# ukmarsbot-wall-sensor-basic.net
KiCad netlist of a schematic drawn in EAGLE
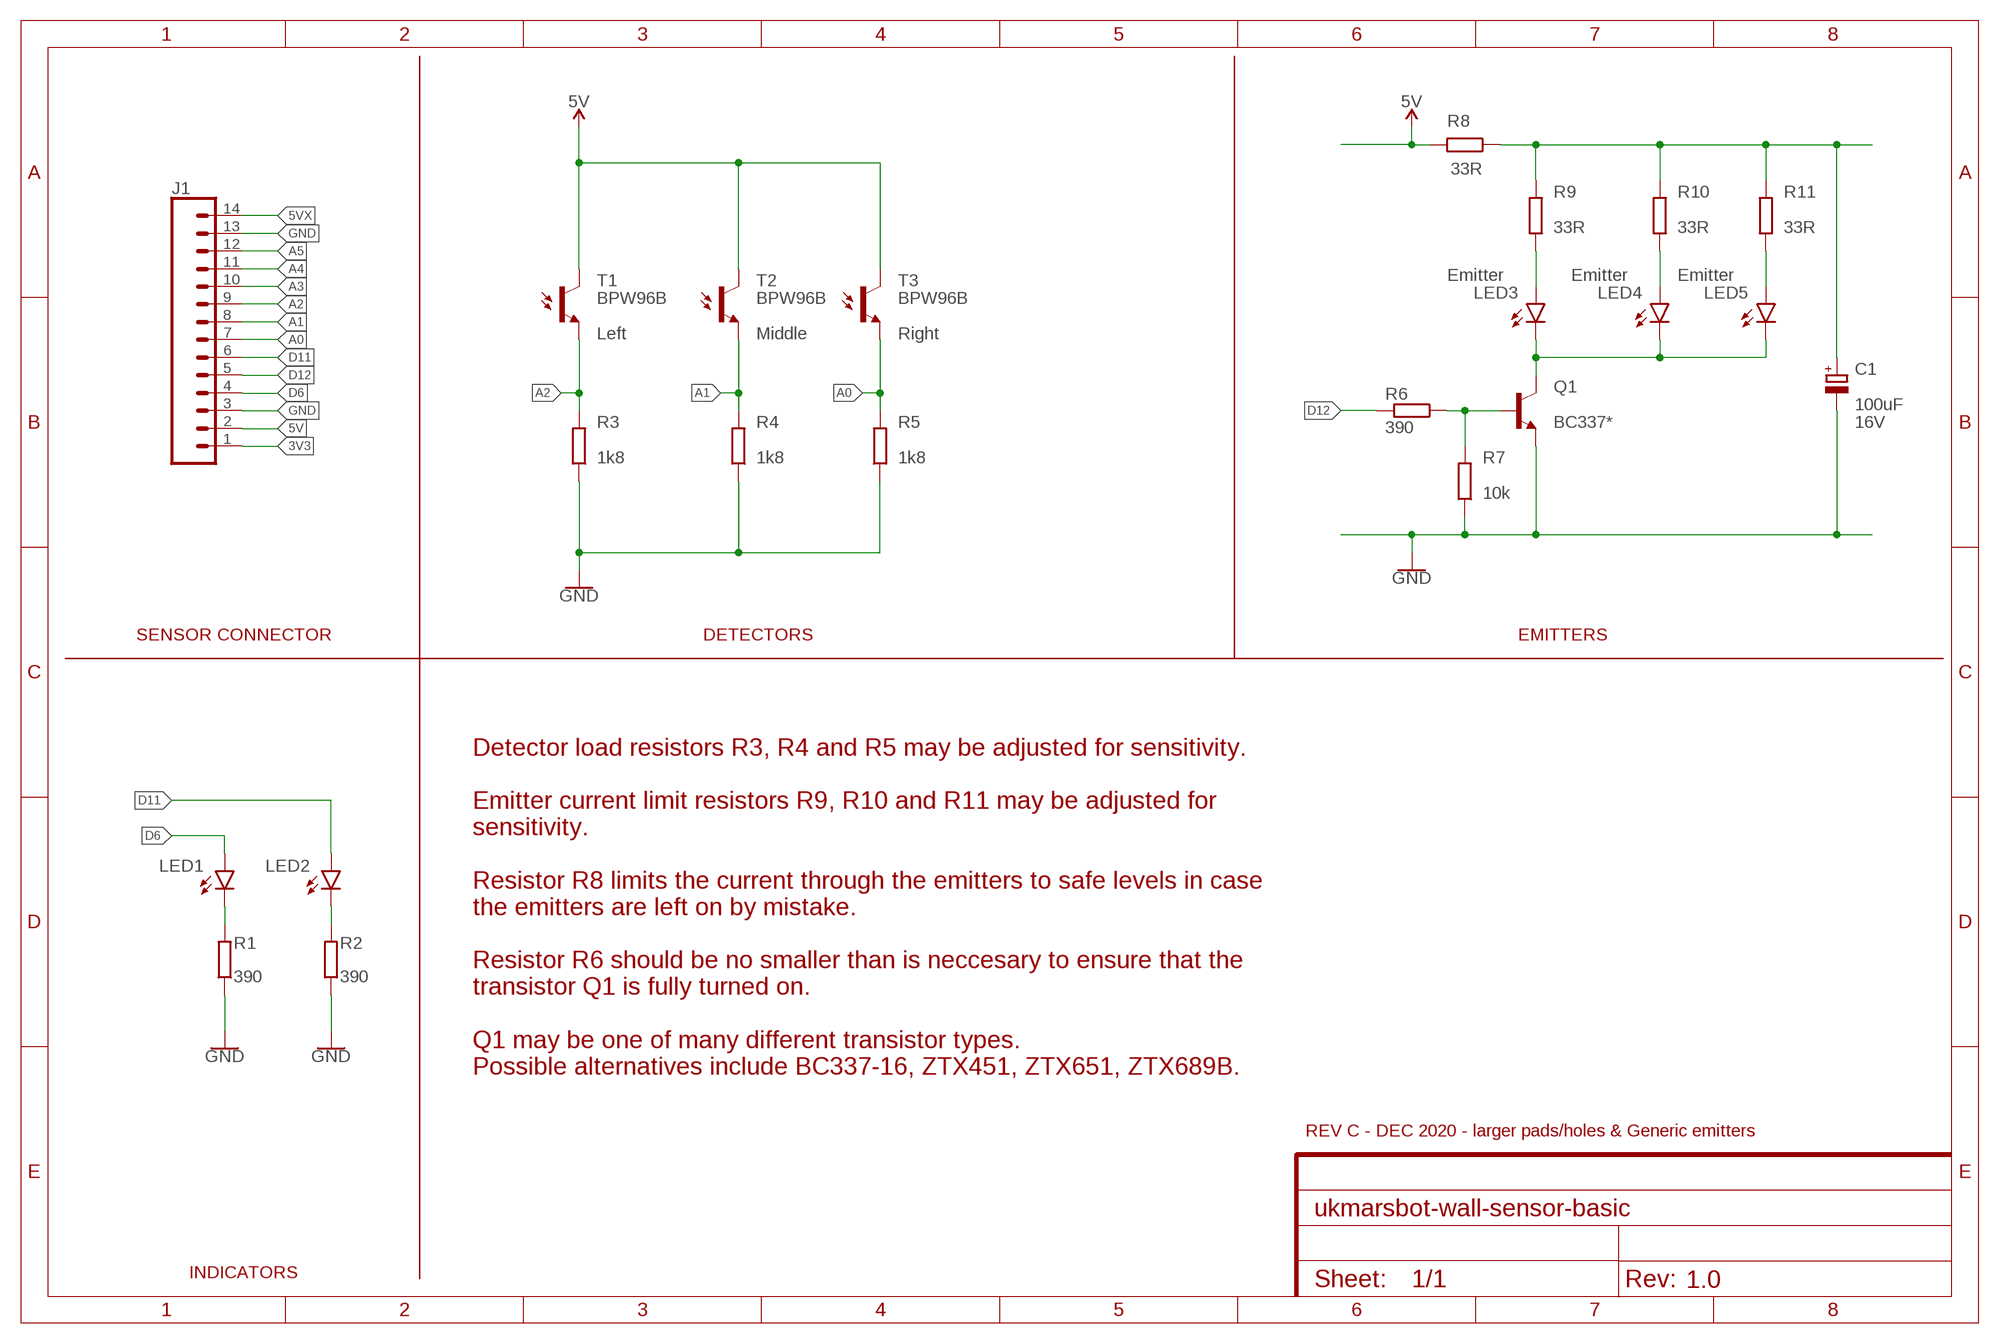
[diagram p0: schematic, sheet 1]

(export (version "E")
  (design (tool "Eeschema 10.0.6"))
  (components
    (comp (ref "C1")
      (value "100uF")
      (footprint "eagle-import:E2,5-7")
      (fields (field (name "VOLTAGE") "16V"))
      (libsource (lib "eagle-import") (part "CPOL-EUE2.5-7"))
    )
    (comp (ref "J1")
      (value "CONN_14")
      (footprint "eagle-import:1X14")
      (libsource (lib "eagle-import") (part "CONN_14"))
    )
    (comp (ref "LED1")
      (value "LED3MM")
      (footprint "eagle-import:LED_3MM")
      (libsource (lib "eagle-import") (part "LED3MM"))
    )
    (comp (ref "LED2")
      (value "LED3MM")
      (footprint "eagle-import:LED_3MM")
      (libsource (lib "eagle-import") (part "LED3MM"))
    )
    (comp (ref "LED3")
      (value "Emitter")
      (footprint "eagle-import:LED-5MM-SIDE")
      (libsource (lib "eagle-import") (part "LED-SIDE"))
    )
    (comp (ref "LED4")
      (value "Emitter")
      (footprint "eagle-import:LED-5MM-SIDE")
      (libsource (lib "eagle-import") (part "LED-SIDE"))
    )
    (comp (ref "LED5")
      (value "Emitter")
      (footprint "eagle-import:LED-5MM-SIDE")
      (libsource (lib "eagle-import") (part "LED-SIDE"))
    )
    (comp (ref "Q1")
      (value "BC337*")
      (footprint "eagle-import:TO92-EBC")
      (libsource (lib "eagle-import") (part "TRANS_NPN"))
    )
    (comp (ref "R1")
      (value "390")
      (footprint "eagle-import:0204_7")
      (libsource (lib "eagle-import") (part "R-EU_0204/7"))
    )
    (comp (ref "R2")
      (value "390")
      (footprint "eagle-import:0204_7")
      (libsource (lib "eagle-import") (part "R-EU_0204/7"))
    )
    (comp (ref "R3")
      (value "1k8")
      (footprint "eagle-import:0204_7")
      (libsource (lib "eagle-import") (part "R-EU_0204/7"))
    )
    (comp (ref "R4")
      (value "1k8")
      (footprint "eagle-import:0204_7")
      (libsource (lib "eagle-import") (part "R-EU_0204/7"))
    )
    (comp (ref "R5")
      (value "1k8")
      (footprint "eagle-import:0204_7")
      (libsource (lib "eagle-import") (part "R-EU_0204/7"))
    )
    (comp (ref "R6")
      (value "390")
      (footprint "eagle-import:0204_7")
      (libsource (lib "eagle-import") (part "R-EU_0204/7"))
    )
    (comp (ref "R7")
      (value "10k")
      (footprint "eagle-import:0204_7")
      (libsource (lib "eagle-import") (part "R-EU_0204/7"))
    )
    (comp (ref "R8")
      (value "33R")
      (footprint "eagle-import:0204_7")
      (libsource (lib "eagle-import") (part "R-EU_0204/7"))
    )
    (comp (ref "R9")
      (value "33R")
      (footprint "eagle-import:0204_7")
      (libsource (lib "eagle-import") (part "R-EU_0204/7"))
    )
    (comp (ref "R10")
      (value "33R")
      (footprint "eagle-import:0204_7")
      (libsource (lib "eagle-import") (part "R-EU_0204/7"))
    )
    (comp (ref "R11")
      (value "33R")
      (footprint "eagle-import:0204_7")
      (libsource (lib "eagle-import") (part "R-EU_0204/7"))
    )
    (comp (ref "T1")
      (value "BPW96B")
      (footprint "eagle-import:PHOTOTRANSISTOR-5MM-SIDE")
      (fields (field (name "POS") "Left"))
      (libsource (lib "eagle-import") (part "PHOTOTRANSISTORSIDE"))
    )
    (comp (ref "T2")
      (value "BPW96B")
      (footprint "eagle-import:PHOTOTRANSISTOR-5MM-SIDE")
      (fields (field (name "POS") "Middle"))
      (libsource (lib "eagle-import") (part "PHOTOTRANSISTORSIDE"))
    )
    (comp (ref "T3")
      (value "BPW96B")
      (footprint "eagle-import:PHOTOTRANSISTOR-5MM-SIDE")
      (fields (field (name "POS") "Right"))
      (libsource (lib "eagle-import") (part "PHOTOTRANSISTORSIDE"))
    )
  )
  (nets
    (net (code "1") (name "3V3") (class "Default")
      (node (ref "J1") (pin "1") (pinfunction "1_1") (pintype "passive"))
    )
    (net (code "2") (name "5V") (class "Default")
      (node (ref "J1") (pin "2") (pinfunction "2_2") (pintype "passive"))
      (node (ref "R8") (pin "2") (pinfunction "2_2") (pintype "passive"))
      (node (ref "T1") (pin "C") (pinfunction "C_C") (pintype "passive"))
      (node (ref "T2") (pin "C") (pinfunction "C_C") (pintype "passive"))
      (node (ref "T3") (pin "C") (pinfunction "C_C") (pintype "passive"))
    )
    (net (code "3") (name "5VX") (class "Default")
      (node (ref "J1") (pin "14") (pinfunction "14_14") (pintype "passive"))
    )
    (net (code "4") (name "A0") (class "Default")
      (node (ref "J1") (pin "7") (pinfunction "7_7") (pintype "passive"))
      (node (ref "R5") (pin "2") (pinfunction "2_2") (pintype "passive"))
      (node (ref "T3") (pin "E") (pinfunction "E_E") (pintype "passive"))
    )
    (net (code "5") (name "A1") (class "Default")
      (node (ref "J1") (pin "8") (pinfunction "8_8") (pintype "passive"))
      (node (ref "R4") (pin "2") (pinfunction "2_2") (pintype "passive"))
      (node (ref "T2") (pin "E") (pinfunction "E_E") (pintype "passive"))
    )
    (net (code "6") (name "A2") (class "Default")
      (node (ref "J1") (pin "9") (pinfunction "9_9") (pintype "passive"))
      (node (ref "R3") (pin "2") (pinfunction "2_2") (pintype "passive"))
      (node (ref "T1") (pin "E") (pinfunction "E_E") (pintype "passive"))
    )
    (net (code "7") (name "A3") (class "Default")
      (node (ref "J1") (pin "10") (pinfunction "10_10") (pintype "passive"))
    )
    (net (code "8") (name "A4") (class "Default")
      (node (ref "J1") (pin "11") (pinfunction "11_11") (pintype "passive"))
    )
    (net (code "9") (name "A5") (class "Default")
      (node (ref "J1") (pin "12") (pinfunction "12_12") (pintype "passive"))
    )
    (net (code "10") (name "D6") (class "Default")
      (node (ref "J1") (pin "4") (pinfunction "4_4") (pintype "passive"))
      (node (ref "LED1") (pin "A") (pinfunction "A_A") (pintype "passive"))
    )
    (net (code "11") (name "D11") (class "Default")
      (node (ref "J1") (pin "6") (pinfunction "6_6") (pintype "passive"))
      (node (ref "LED2") (pin "A") (pinfunction "A_A") (pintype "passive"))
    )
    (net (code "12") (name "D12") (class "Default")
      (node (ref "J1") (pin "5") (pinfunction "5_5") (pintype "passive"))
      (node (ref "R6") (pin "2") (pinfunction "2_2") (pintype "passive"))
    )
    (net (code "13") (name "GND") (class "Default")
      (node (ref "C1") (pin "-") (pinfunction "-_-") (pintype "passive"))
      (node (ref "J1") (pin "13") (pinfunction "13_13") (pintype "passive"))
      (node (ref "J1") (pin "3") (pinfunction "3_3") (pintype "passive"))
      (node (ref "Q1") (pin "E") (pinfunction "E_E") (pintype "passive"))
      (node (ref "R1") (pin "1") (pinfunction "1_1") (pintype "passive"))
      (node (ref "R2") (pin "1") (pinfunction "1_1") (pintype "passive"))
      (node (ref "R3") (pin "1") (pinfunction "1_1") (pintype "passive"))
      (node (ref "R4") (pin "1") (pinfunction "1_1") (pintype "passive"))
      (node (ref "R5") (pin "1") (pinfunction "1_1") (pintype "passive"))
      (node (ref "R7") (pin "1") (pinfunction "1_1") (pintype "passive"))
    )
    (net (code "14") (name "Net-(C1-Pad+)") (class "Default")
      (node (ref "C1") (pin "+") (pinfunction "+_+") (pintype "passive"))
      (node (ref "R10") (pin "2") (pinfunction "2_2") (pintype "passive"))
      (node (ref "R11") (pin "2") (pinfunction "2_2") (pintype "passive"))
      (node (ref "R8") (pin "1") (pinfunction "1_1") (pintype "passive"))
      (node (ref "R9") (pin "2") (pinfunction "2_2") (pintype "passive"))
    )
    (net (code "15") (name "Net-(LED1-C)") (class "Default")
      (node (ref "LED1") (pin "K") (pinfunction "C_K") (pintype "passive"))
      (node (ref "R1") (pin "2") (pinfunction "2_2") (pintype "passive"))
    )
    (net (code "16") (name "Net-(LED2-C)") (class "Default")
      (node (ref "LED2") (pin "K") (pinfunction "C_K") (pintype "passive"))
      (node (ref "R2") (pin "2") (pinfunction "2_2") (pintype "passive"))
    )
    (net (code "17") (name "Net-(LED3-C)") (class "Default")
      (node (ref "LED3") (pin "K") (pinfunction "C_K") (pintype "passive"))
      (node (ref "LED4") (pin "K") (pinfunction "C_K") (pintype "passive"))
      (node (ref "LED5") (pin "K") (pinfunction "C_K") (pintype "passive"))
      (node (ref "Q1") (pin "C") (pinfunction "C_C") (pintype "passive"))
    )
    (net (code "18") (name "Net-(LED3-PadA)") (class "Default")
      (node (ref "LED3") (pin "A") (pinfunction "A_A") (pintype "passive"))
      (node (ref "R9") (pin "1") (pinfunction "1_1") (pintype "passive"))
    )
    (net (code "19") (name "Net-(LED4-PadA)") (class "Default")
      (node (ref "LED4") (pin "A") (pinfunction "A_A") (pintype "passive"))
      (node (ref "R10") (pin "1") (pinfunction "1_1") (pintype "passive"))
    )
    (net (code "20") (name "Net-(LED5-PadA)") (class "Default")
      (node (ref "LED5") (pin "A") (pinfunction "A_A") (pintype "passive"))
      (node (ref "R11") (pin "1") (pinfunction "1_1") (pintype "passive"))
    )
    (net (code "21") (name "Net-(Q1-PadB)") (class "Default")
      (node (ref "Q1") (pin "B") (pinfunction "B_B") (pintype "passive"))
      (node (ref "R6") (pin "1") (pinfunction "1_1") (pintype "passive"))
      (node (ref "R7") (pin "2") (pinfunction "2_2") (pintype "passive"))
    )
  )
)
